# Interface_V3.net
KiCad netlist of a schematic drawn in EAGLE
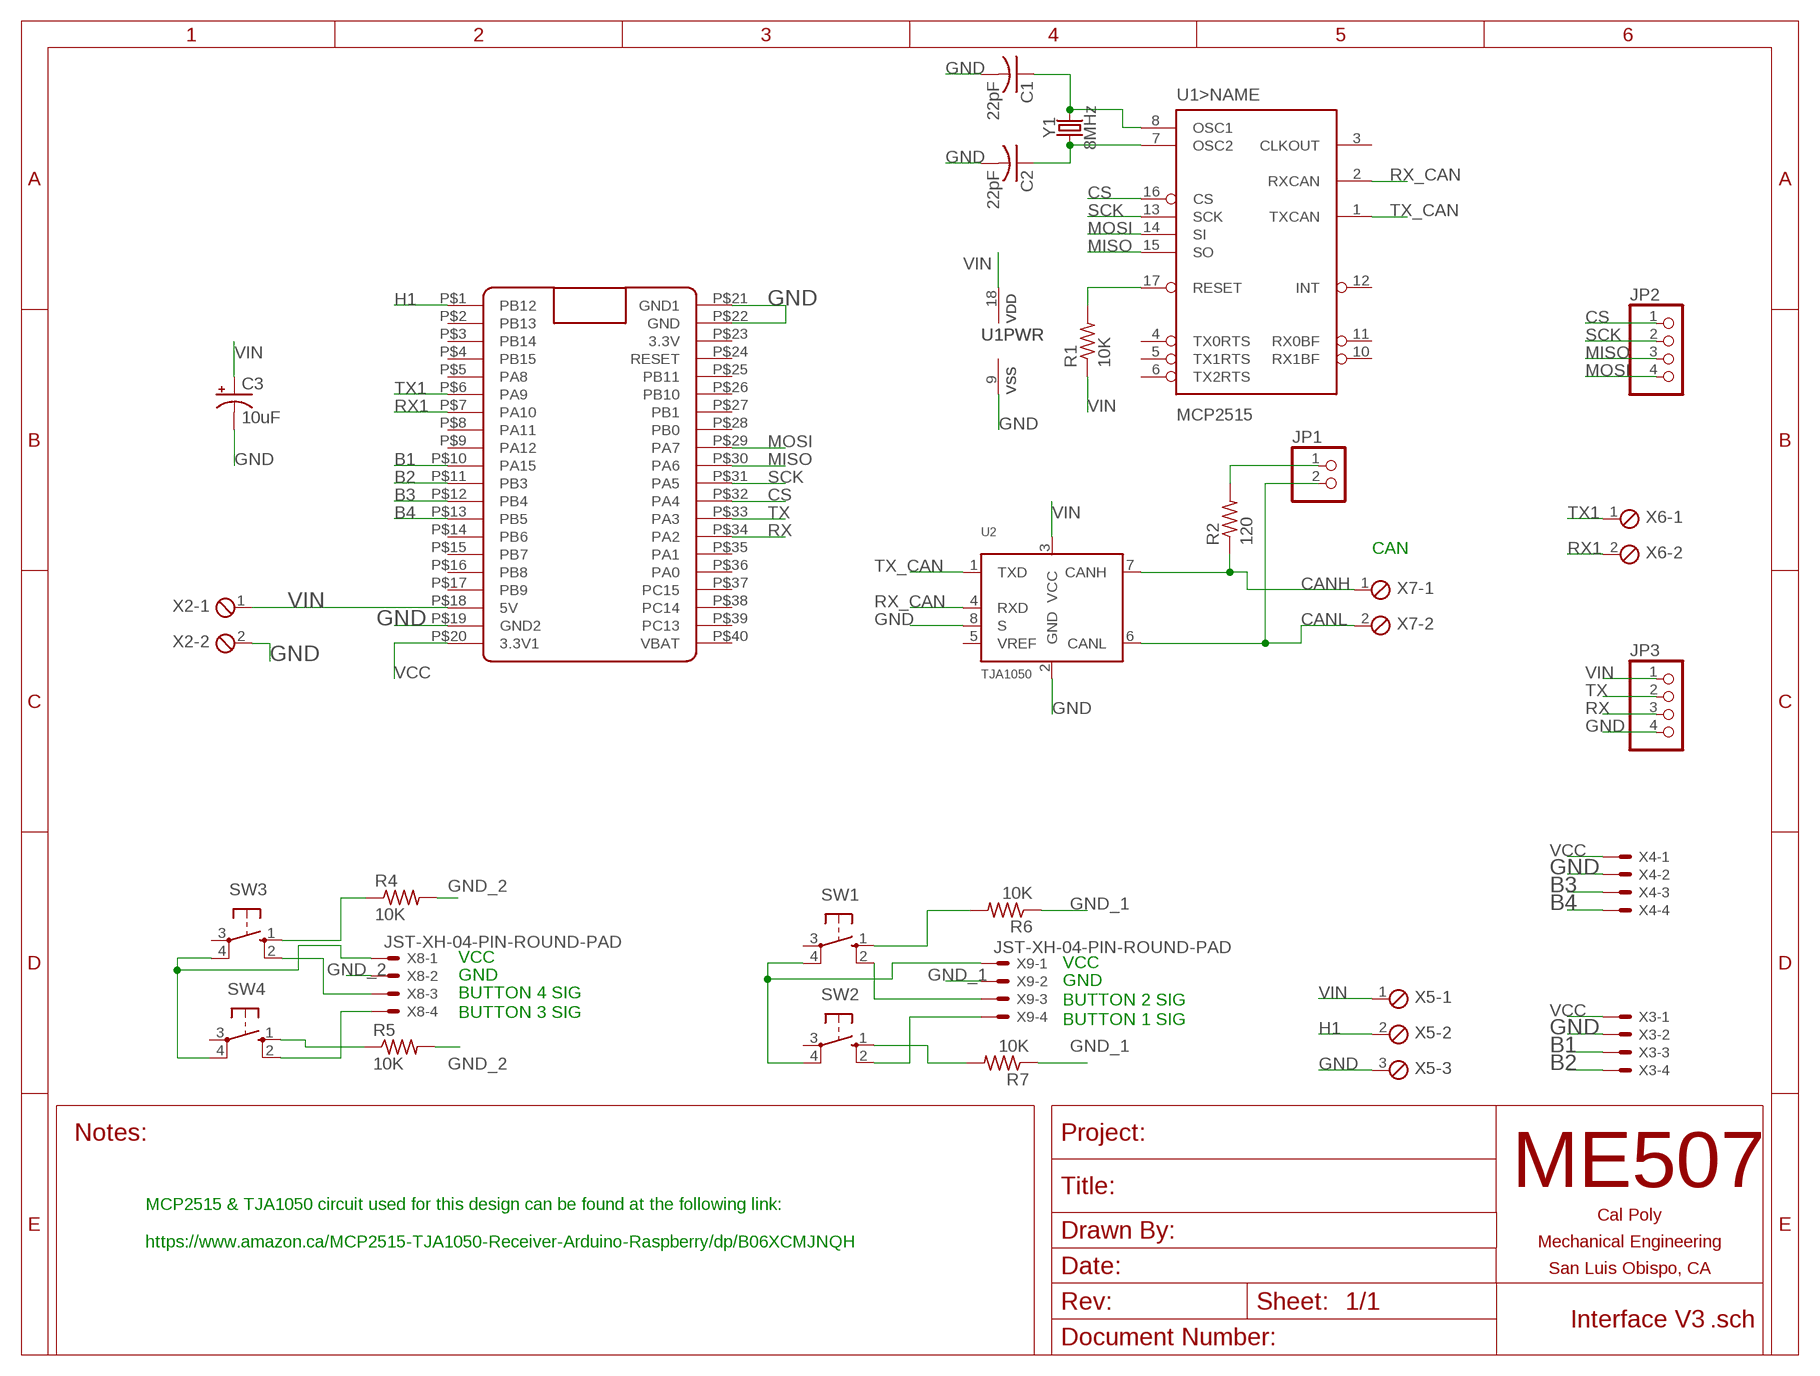
[diagram p0: schematic, sheet 1]

(export (version "E")
  (design (tool "Eeschema 10.0.6"))
  (components
    (comp (ref "C1")
      (value "22pF")
      (footprint "eagle-import:C0805")
      (libsource (lib "eagle-import") (part "C-USC0805"))
    )
    (comp (ref "C2")
      (value "22pF")
      (footprint "eagle-import:C0805")
      (libsource (lib "eagle-import") (part "C-USC0805"))
    )
    (comp (ref "C3")
      (value "10uF")
      (footprint "eagle-import:CT3216")
      (libsource (lib "eagle-import") (part "CPOL-USCT3216"))
    )
    (comp (ref "JP1")
      (value "PINHD-1X2")
      (footprint "eagle-import:1X02")
      (libsource (lib "eagle-import") (part "PINHD-1X2"))
    )
    (comp (ref "JP2")
      (value "PINHD-1X4")
      (footprint "eagle-import:1X04")
      (libsource (lib "eagle-import") (part "PINHD-1X4"))
    )
    (comp (ref "JP3")
      (value "PINHD-1X4")
      (footprint "eagle-import:1X04")
      (libsource (lib "eagle-import") (part "PINHD-1X4"))
    )
    (comp (ref "R1")
      (value "10K")
      (footprint "eagle-import:R0805")
      (libsource (lib "eagle-import") (part "R-US_R0805"))
    )
    (comp (ref "R2")
      (value "120")
      (footprint "eagle-import:R0805")
      (libsource (lib "eagle-import") (part "R-US_R0805"))
    )
    (comp (ref "R4")
      (value "10K")
      (footprint "eagle-import:R0805")
      (libsource (lib "eagle-import") (part "R-US_R0805"))
    )
    (comp (ref "R5")
      (value "10K")
      (footprint "eagle-import:R0805")
      (libsource (lib "eagle-import") (part "R-US_R0805"))
    )
    (comp (ref "R6")
      (value "10K")
      (footprint "eagle-import:R0805")
      (libsource (lib "eagle-import") (part "R-US_R0805"))
    )
    (comp (ref "R7")
      (value "10K")
      (footprint "eagle-import:R0805")
      (libsource (lib "eagle-import") (part "R-US_R0805"))
    )
    (comp (ref "SW1")
      (value "PUSHBUTTON")
      (footprint "eagle-import:B3F-10XX")
      (fields (field (name "MPN") "B3F-1000"))
      (libsource (lib "eagle-import") (part "PUSHBUTTON"))
    )
    (comp (ref "SW2")
      (value "PUSHBUTTON")
      (footprint "eagle-import:B3F-10XX")
      (fields (field (name "MPN") "B3F-1000"))
      (libsource (lib "eagle-import") (part "PUSHBUTTON"))
    )
    (comp (ref "SW3")
      (value "PUSHBUTTON")
      (footprint "eagle-import:B3F-10XX")
      (fields (field (name "MPN") "B3F-1000"))
      (libsource (lib "eagle-import") (part "PUSHBUTTON"))
    )
    (comp (ref "SW4")
      (value "PUSHBUTTON")
      (footprint "eagle-import:B3F-10XX")
      (fields (field (name "MPN") "B3F-1000"))
      (libsource (lib "eagle-import") (part "PUSHBUTTON"))
    )
    (comp (ref "U$1")
      (value "BLUE_PILL")
      (footprint "eagle-import:BLUE_PILL")
      (libsource (lib "eagle-import") (part "BLUE_PILL"))
    )
    (comp (ref "U1")
      (value "MCP2515")
      (footprint "eagle-import:SO18W")
      (libsource (lib "eagle-import") (part "MCP2515(MCP2510)SO"))
    )
    (comp (ref "U2")
      (value "TJA1050")
      (footprint "eagle-import:SOT96-1")
      (fields (field (name "MF") "NXP USA"))
      (libsource (lib "eagle-import") (part "TJA1050"))
    )
    (comp (ref "X2")
      (value "SCREWTERM_2P_381")
      (footprint "eagle-import:2POL381")
      (libsource (lib "eagle-import") (part "SCREWTERM_2P_381"))
    )
    (comp (ref "X3")
      (value "JST-XH-04-PIN-LONG-PAD")
      (footprint "eagle-import:JST-XH-04-PACKAGE-LONG-PAD")
      (libsource (lib "eagle-import") (part "JST-XH-04-PIN-LONG-PAD"))
    )
    (comp (ref "X4")
      (value "JST-XH-04-PIN-LONG-PAD")
      (footprint "eagle-import:JST-XH-04-PACKAGE-LONG-PAD")
      (libsource (lib "eagle-import") (part "JST-XH-04-PIN-LONG-PAD"))
    )
    (comp (ref "X5")
      (value "SCREWTERM_3P_381")
      (footprint "eagle-import:3POL381")
      (libsource (lib "eagle-import") (part "SCREWTERM_3P_381"))
    )
    (comp (ref "X6")
      (value "SCREWTERM_2P_381")
      (footprint "eagle-import:2POL381")
      (libsource (lib "eagle-import") (part "SCREWTERM_2P_381"))
    )
    (comp (ref "X7")
      (value "SCREWTERM_2P_381")
      (footprint "eagle-import:2POL381")
      (libsource (lib "eagle-import") (part "SCREWTERM_2P_381"))
    )
    (comp (ref "X8")
      (value "JST-XH-04-PIN-ROUND-PAD")
      (footprint "eagle-import:JST-XH-04-PACKAGE-ROUND-PAD")
      (libsource (lib "eagle-import") (part "JST-XH-04-PIN-ROUND-PAD"))
    )
    (comp (ref "X9")
      (value "JST-XH-04-PIN-ROUND-PAD")
      (footprint "eagle-import:JST-XH-04-PACKAGE-ROUND-PAD")
      (libsource (lib "eagle-import") (part "JST-XH-04-PIN-ROUND-PAD"))
    )
    (comp (ref "Y1")
      (value "8MHz")
      (footprint "eagle-import:HC49US")
      (libsource (lib "eagle-import") (part "CRYSTALPTH-HC49US"))
    )
  )
  (nets
    (net (code "1") (name "/B1") (class "Default")
      (node (ref "U$1") (pin "P$10") (pinfunction "PA15_P$10") (pintype "bidirectional"))
      (node (ref "X3") (pin "3") (pinfunction "S_3") (pintype "passive"))
    )
    (net (code "2") (name "/B2") (class "Default")
      (node (ref "U$1") (pin "P$11") (pinfunction "PB3_P$11") (pintype "bidirectional"))
      (node (ref "X3") (pin "4") (pinfunction "S_4") (pintype "passive"))
    )
    (net (code "3") (name "/B3") (class "Default")
      (node (ref "U$1") (pin "P$12") (pinfunction "PB4_P$12") (pintype "bidirectional"))
      (node (ref "X4") (pin "3") (pinfunction "S_3") (pintype "passive"))
    )
    (net (code "4") (name "/B4") (class "Default")
      (node (ref "U$1") (pin "P$13") (pinfunction "PB5_P$13") (pintype "bidirectional"))
      (node (ref "X4") (pin "4") (pinfunction "S_4") (pintype "passive"))
    )
    (net (code "5") (name "/CANH") (class "Default")
      (node (ref "R2") (pin "1") (pinfunction "1_1") (pintype "passive"))
      (node (ref "U2") (pin "7") (pinfunction "CANH_7") (pintype "bidirectional"))
      (node (ref "X7") (pin "1") (pinfunction "1_1") (pintype "passive"))
    )
    (net (code "6") (name "/CANL") (class "Default")
      (node (ref "JP1") (pin "2") (pinfunction "2_2") (pintype "passive"))
      (node (ref "U2") (pin "6") (pinfunction "CANL_6") (pintype "bidirectional"))
      (node (ref "X7") (pin "2") (pinfunction "1_2") (pintype "passive"))
    )
    (net (code "7") (name "/CS") (class "Default")
      (node (ref "JP2") (pin "1") (pinfunction "1_1") (pintype "passive"))
      (node (ref "U$1") (pin "P$32") (pinfunction "PA4_P$32") (pintype "bidirectional"))
      (node (ref "U1") (pin "16") (pinfunction "CS_16") (pintype "input"))
    )
    (net (code "8") (name "/GND") (class "Default")
      (node (ref "C1") (pin "2") (pinfunction "2_2") (pintype "passive"))
      (node (ref "C2") (pin "2") (pinfunction "2_2") (pintype "passive"))
      (node (ref "C3") (pin "-") (pinfunction "-_-") (pintype "passive"))
      (node (ref "JP3") (pin "4") (pinfunction "4_4") (pintype "passive"))
      (node (ref "U$1") (pin "P$19") (pinfunction "GND2_P$19") (pintype "bidirectional"))
      (node (ref "U$1") (pin "P$21") (pinfunction "GND1_P$21") (pintype "power_in"))
      (node (ref "U$1") (pin "P$22") (pinfunction "GND_P$22") (pintype "bidirectional"))
      (node (ref "U1") (pin "9") (pinfunction "VSS_9") (pintype "power_in"))
      (node (ref "U2") (pin "2") (pinfunction "GND_2") (pintype "bidirectional"))
      (node (ref "U2") (pin "8") (pinfunction "S_8") (pintype "power_in"))
      (node (ref "X2") (pin "2") (pinfunction "1_2") (pintype "passive"))
      (node (ref "X3") (pin "2") (pinfunction "S_2") (pintype "passive"))
      (node (ref "X4") (pin "2") (pinfunction "S_2") (pintype "passive"))
      (node (ref "X5") (pin "3") (pinfunction "1_3") (pintype "passive"))
    )
    (net (code "9") (name "/GND_1") (class "Default")
      (node (ref "R6") (pin "1") (pinfunction "1_1") (pintype "passive"))
      (node (ref "R7") (pin "1") (pinfunction "1_1") (pintype "passive"))
      (node (ref "X9") (pin "2") (pinfunction "S_2") (pintype "passive"))
    )
    (net (code "10") (name "/GND_2") (class "Default")
      (node (ref "R4") (pin "2") (pinfunction "2_2") (pintype "passive"))
      (node (ref "R5") (pin "2") (pinfunction "2_2") (pintype "passive"))
      (node (ref "X8") (pin "2") (pinfunction "S_2") (pintype "passive"))
    )
    (net (code "11") (name "/H1") (class "Default")
      (node (ref "U$1") (pin "P$1") (pinfunction "PB12_P$1") (pintype "bidirectional"))
      (node (ref "X5") (pin "2") (pinfunction "1_2") (pintype "passive"))
    )
    (net (code "12") (name "/MISO") (class "Default")
      (node (ref "JP2") (pin "3") (pinfunction "3_3") (pintype "passive"))
      (node (ref "U$1") (pin "P$30") (pinfunction "PA6_P$30") (pintype "bidirectional"))
      (node (ref "U1") (pin "15") (pinfunction "SO_15") (pintype "output"))
    )
    (net (code "13") (name "/MOSI") (class "Default")
      (node (ref "JP2") (pin "4") (pinfunction "4_4") (pintype "passive"))
      (node (ref "U$1") (pin "P$29") (pinfunction "PA7_P$29") (pintype "bidirectional"))
      (node (ref "U1") (pin "14") (pinfunction "SI_14") (pintype "input"))
    )
    (net (code "14") (name "/RX") (class "Default")
      (node (ref "JP3") (pin "3") (pinfunction "3_3") (pintype "passive"))
      (node (ref "U$1") (pin "P$34") (pinfunction "PA2_P$34") (pintype "bidirectional"))
    )
    (net (code "15") (name "/RX1") (class "Default")
      (node (ref "U$1") (pin "P$7") (pinfunction "PA10_P$7") (pintype "bidirectional"))
      (node (ref "X6") (pin "2") (pinfunction "1_2") (pintype "passive"))
    )
    (net (code "16") (name "/RX_CAN") (class "Default")
      (node (ref "U1") (pin "2") (pinfunction "RXCAN_2") (pintype "input"))
      (node (ref "U2") (pin "4") (pinfunction "RXD_4") (pintype "bidirectional"))
    )
    (net (code "17") (name "/SCK") (class "Default")
      (node (ref "JP2") (pin "2") (pinfunction "2_2") (pintype "passive"))
      (node (ref "U$1") (pin "P$31") (pinfunction "PA5_P$31") (pintype "bidirectional"))
      (node (ref "U1") (pin "13") (pinfunction "SCK_13") (pintype "input"))
    )
    (net (code "18") (name "/TX") (class "Default")
      (node (ref "JP3") (pin "2") (pinfunction "2_2") (pintype "passive"))
      (node (ref "U$1") (pin "P$33") (pinfunction "PA3_P$33") (pintype "bidirectional"))
    )
    (net (code "19") (name "/TX1") (class "Default")
      (node (ref "U$1") (pin "P$6") (pinfunction "PA9_P$6") (pintype "bidirectional"))
      (node (ref "X6") (pin "1") (pinfunction "1_1") (pintype "passive"))
    )
    (net (code "20") (name "/TX_CAN") (class "Default")
      (node (ref "U1") (pin "1") (pinfunction "TXCAN_1") (pintype "output"))
      (node (ref "U2") (pin "1") (pinfunction "TXD_1") (pintype "output"))
    )
    (net (code "21") (name "/VCC") (class "Default")
      (node (ref "U$1") (pin "P$20") (pinfunction "3.3V1_P$20") (pintype "bidirectional"))
      (node (ref "X3") (pin "1") (pinfunction "S_1") (pintype "passive"))
      (node (ref "X4") (pin "1") (pinfunction "S_1") (pintype "passive"))
    )
    (net (code "22") (name "/VIN") (class "Default")
      (node (ref "C3") (pin "+") (pinfunction "+_+") (pintype "passive"))
      (node (ref "JP3") (pin "1") (pinfunction "1_1") (pintype "passive"))
      (node (ref "R1") (pin "1") (pinfunction "1_1") (pintype "passive"))
      (node (ref "U$1") (pin "P$18") (pinfunction "5V_P$18") (pintype "bidirectional"))
      (node (ref "U1") (pin "18") (pinfunction "VDD_18") (pintype "power_in"))
      (node (ref "U2") (pin "3") (pinfunction "VCC_3") (pintype "bidirectional"))
      (node (ref "X2") (pin "1") (pinfunction "1_1") (pintype "passive"))
      (node (ref "X5") (pin "1") (pinfunction "1_1") (pintype "passive"))
    )
    (net (code "23") (name "Net-(JP1-Pad1)") (class "Default")
      (node (ref "JP1") (pin "1") (pinfunction "1_1") (pintype "passive"))
      (node (ref "R2") (pin "2") (pinfunction "2_2") (pintype "passive"))
    )
    (net (code "24") (name "Net-(SW1-P1)") (class "Default")
      (node (ref "SW1") (pin "4") (pinfunction "P1_4") (pintype "passive"))
      (node (ref "SW2") (pin "4") (pinfunction "P1_4") (pintype "passive"))
      (node (ref "X9") (pin "1") (pinfunction "S_1") (pintype "passive"))
    )
    (net (code "25") (name "Net-(SW1-S)") (class "Default")
      (node (ref "R6") (pin "2") (pinfunction "2_2") (pintype "passive"))
      (node (ref "SW1") (pin "1") (pinfunction "S_1") (pintype "passive"))
    )
    (net (code "26") (name "Net-(SW1-S1)") (class "Default")
      (node (ref "SW1") (pin "2") (pinfunction "S1_2") (pintype "passive"))
      (node (ref "X9") (pin "3") (pinfunction "S_3") (pintype "passive"))
    )
    (net (code "27") (name "Net-(SW2-S)") (class "Default")
      (node (ref "R7") (pin "2") (pinfunction "2_2") (pintype "passive"))
      (node (ref "SW2") (pin "1") (pinfunction "S_1") (pintype "passive"))
    )
    (net (code "28") (name "Net-(SW2-S1)") (class "Default")
      (node (ref "SW2") (pin "2") (pinfunction "S1_2") (pintype "passive"))
      (node (ref "X9") (pin "4") (pinfunction "S_4") (pintype "passive"))
    )
    (net (code "29") (name "Net-(SW3-P1)") (class "Default")
      (node (ref "SW3") (pin "4") (pinfunction "P1_4") (pintype "passive"))
      (node (ref "SW4") (pin "4") (pinfunction "P1_4") (pintype "passive"))
      (node (ref "X8") (pin "1") (pinfunction "S_1") (pintype "passive"))
    )
    (net (code "30") (name "Net-(SW3-S)") (class "Default")
      (node (ref "R4") (pin "1") (pinfunction "1_1") (pintype "passive"))
      (node (ref "SW3") (pin "1") (pinfunction "S_1") (pintype "passive"))
    )
    (net (code "31") (name "Net-(SW3-S1)") (class "Default")
      (node (ref "SW3") (pin "2") (pinfunction "S1_2") (pintype "passive"))
      (node (ref "X8") (pin "3") (pinfunction "S_3") (pintype "passive"))
    )
    (net (code "32") (name "Net-(SW4-S)") (class "Default")
      (node (ref "R5") (pin "1") (pinfunction "1_1") (pintype "passive"))
      (node (ref "SW4") (pin "1") (pinfunction "S_1") (pintype "passive"))
    )
    (net (code "33") (name "Net-(SW4-S1)") (class "Default")
      (node (ref "SW4") (pin "2") (pinfunction "S1_2") (pintype "passive"))
      (node (ref "X8") (pin "4") (pinfunction "S_4") (pintype "passive"))
    )
    (net (code "34") (name "Net-(U1A-OSC1)") (class "Default")
      (node (ref "C1") (pin "1") (pinfunction "1_1") (pintype "passive"))
      (node (ref "U1") (pin "8") (pinfunction "OSC1_8") (pintype "input"))
      (node (ref "Y1") (pin "2") (pinfunction "2_2") (pintype "passive"))
    )
    (net (code "35") (name "Net-(U1A-OSC2)") (class "Default")
      (node (ref "C2") (pin "1") (pinfunction "1_1") (pintype "passive"))
      (node (ref "U1") (pin "7") (pinfunction "OSC2_7") (pintype "output"))
      (node (ref "Y1") (pin "1") (pinfunction "1_1") (pintype "passive"))
    )
    (net (code "36") (name "Net-(U1A-RESET)") (class "Default")
      (node (ref "R1") (pin "2") (pinfunction "2_2") (pintype "passive"))
      (node (ref "U1") (pin "17") (pinfunction "RESET_17") (pintype "input"))
    )
    (net (code "37") (name "unconnected-(SW1-P-Pad3)") (class "Default")
      (node (ref "SW1") (pin "3") (pinfunction "P_3") (pintype "passive"))
    )
    (net (code "38") (name "unconnected-(SW2-P-Pad3)") (class "Default")
      (node (ref "SW2") (pin "3") (pinfunction "P_3") (pintype "passive"))
    )
    (net (code "39") (name "unconnected-(SW3-P-Pad3)") (class "Default")
      (node (ref "SW3") (pin "3") (pinfunction "P_3") (pintype "passive"))
    )
    (net (code "40") (name "unconnected-(SW4-P-Pad3)") (class "Default")
      (node (ref "SW4") (pin "3") (pinfunction "P_3") (pintype "passive"))
    )
    (net (code "41") (name "unconnected-(U$1-3.3V-PadP$23)") (class "Default")
      (node (ref "U$1") (pin "P$23") (pinfunction "3.3V_P$23") (pintype "bidirectional"))
    )
    (net (code "42") (name "unconnected-(U$1-PA0-PadP$36)") (class "Default")
      (node (ref "U$1") (pin "P$36") (pinfunction "PA0_P$36") (pintype "bidirectional"))
    )
    (net (code "43") (name "unconnected-(U$1-PA1-PadP$35)") (class "Default")
      (node (ref "U$1") (pin "P$35") (pinfunction "PA1_P$35") (pintype "bidirectional"))
    )
    (net (code "44") (name "unconnected-(U$1-PA8-PadP$5)") (class "Default")
      (node (ref "U$1") (pin "P$5") (pinfunction "PA8_P$5") (pintype "bidirectional"))
    )
    (net (code "45") (name "unconnected-(U$1-PA11-PadP$8)") (class "Default")
      (node (ref "U$1") (pin "P$8") (pinfunction "PA11_P$8") (pintype "bidirectional"))
    )
    (net (code "46") (name "unconnected-(U$1-PA12-PadP$9)") (class "Default")
      (node (ref "U$1") (pin "P$9") (pinfunction "PA12_P$9") (pintype "bidirectional"))
    )
    (net (code "47") (name "unconnected-(U$1-PB0-PadP$28)") (class "Default")
      (node (ref "U$1") (pin "P$28") (pinfunction "PB0_P$28") (pintype "bidirectional"))
    )
    (net (code "48") (name "unconnected-(U$1-PB1-PadP$27)") (class "Default")
      (node (ref "U$1") (pin "P$27") (pinfunction "PB1_P$27") (pintype "bidirectional"))
    )
    (net (code "49") (name "unconnected-(U$1-PB6-PadP$14)") (class "Default")
      (node (ref "U$1") (pin "P$14") (pinfunction "PB6_P$14") (pintype "bidirectional"))
    )
    (net (code "50") (name "unconnected-(U$1-PB7-PadP$15)") (class "Default")
      (node (ref "U$1") (pin "P$15") (pinfunction "PB7_P$15") (pintype "bidirectional"))
    )
    (net (code "51") (name "unconnected-(U$1-PB8-PadP$16)") (class "Default")
      (node (ref "U$1") (pin "P$16") (pinfunction "PB8_P$16") (pintype "bidirectional"))
    )
    (net (code "52") (name "unconnected-(U$1-PB9-PadP$17)") (class "Default")
      (node (ref "U$1") (pin "P$17") (pinfunction "PB9_P$17") (pintype "bidirectional"))
    )
    (net (code "53") (name "unconnected-(U$1-PB10-PadP$26)") (class "Default")
      (node (ref "U$1") (pin "P$26") (pinfunction "PB10_P$26") (pintype "bidirectional"))
    )
    (net (code "54") (name "unconnected-(U$1-PB11-PadP$25)") (class "Default")
      (node (ref "U$1") (pin "P$25") (pinfunction "PB11_P$25") (pintype "bidirectional"))
    )
    (net (code "55") (name "unconnected-(U$1-PB13-PadP$2)") (class "Default")
      (node (ref "U$1") (pin "P$2") (pinfunction "PB13_P$2") (pintype "bidirectional"))
    )
    (net (code "56") (name "unconnected-(U$1-PB14-PadP$3)") (class "Default")
      (node (ref "U$1") (pin "P$3") (pinfunction "PB14_P$3") (pintype "bidirectional"))
    )
    (net (code "57") (name "unconnected-(U$1-PB15-PadP$4)") (class "Default")
      (node (ref "U$1") (pin "P$4") (pinfunction "PB15_P$4") (pintype "bidirectional"))
    )
    (net (code "58") (name "unconnected-(U$1-PC13-PadP$39)") (class "Default")
      (node (ref "U$1") (pin "P$39") (pinfunction "PC13_P$39") (pintype "bidirectional"))
    )
    (net (code "59") (name "unconnected-(U$1-PC14-PadP$38)") (class "Default")
      (node (ref "U$1") (pin "P$38") (pinfunction "PC14_P$38") (pintype "bidirectional"))
    )
    (net (code "60") (name "unconnected-(U$1-PC15-PadP$37)") (class "Default")
      (node (ref "U$1") (pin "P$37") (pinfunction "PC15_P$37") (pintype "bidirectional"))
    )
    (net (code "61") (name "unconnected-(U$1-RESET-PadP$24)") (class "Default")
      (node (ref "U$1") (pin "P$24") (pinfunction "RESET_P$24") (pintype "bidirectional"))
    )
    (net (code "62") (name "unconnected-(U$1-VBAT-PadP$40)") (class "Default")
      (node (ref "U$1") (pin "P$40") (pinfunction "VBAT_P$40") (pintype "bidirectional"))
    )
    (net (code "63") (name "unconnected-(U1A-CLKOUT-Pad3)") (class "Default")
      (node (ref "U1") (pin "3") (pinfunction "CLKOUT_3") (pintype "output"))
    )
    (net (code "64") (name "unconnected-(U1A-INT-Pad12)") (class "Default")
      (node (ref "U1") (pin "12") (pinfunction "INT_12") (pintype "output"))
    )
    (net (code "65") (name "unconnected-(U1A-RX0BF-Pad11)") (class "Default")
      (node (ref "U1") (pin "11") (pinfunction "RX0BF_11") (pintype "output"))
    )
    (net (code "66") (name "unconnected-(U1A-RX1BF-Pad10)") (class "Default")
      (node (ref "U1") (pin "10") (pinfunction "RX1BF_10") (pintype "output"))
    )
    (net (code "67") (name "unconnected-(U1A-TX0RTS-Pad4)") (class "Default")
      (node (ref "U1") (pin "4") (pinfunction "TX0RTS_4") (pintype "input"))
    )
    (net (code "68") (name "unconnected-(U1A-TX1RTS-Pad5)") (class "Default")
      (node (ref "U1") (pin "5") (pinfunction "TX1RTS_5") (pintype "input"))
    )
    (net (code "69") (name "unconnected-(U1A-TX2RTS-Pad6)") (class "Default")
      (node (ref "U1") (pin "6") (pinfunction "TX2RTS_6") (pintype "input"))
    )
    (net (code "70") (name "unconnected-(U2-VREF-Pad5)") (class "Default")
      (node (ref "U2") (pin "5") (pinfunction "VREF_5") (pintype "passive"))
    )
  )
)
